# ArbPwrBoost_P4.net
KiCad netlist of a schematic drawn in Altium Designer
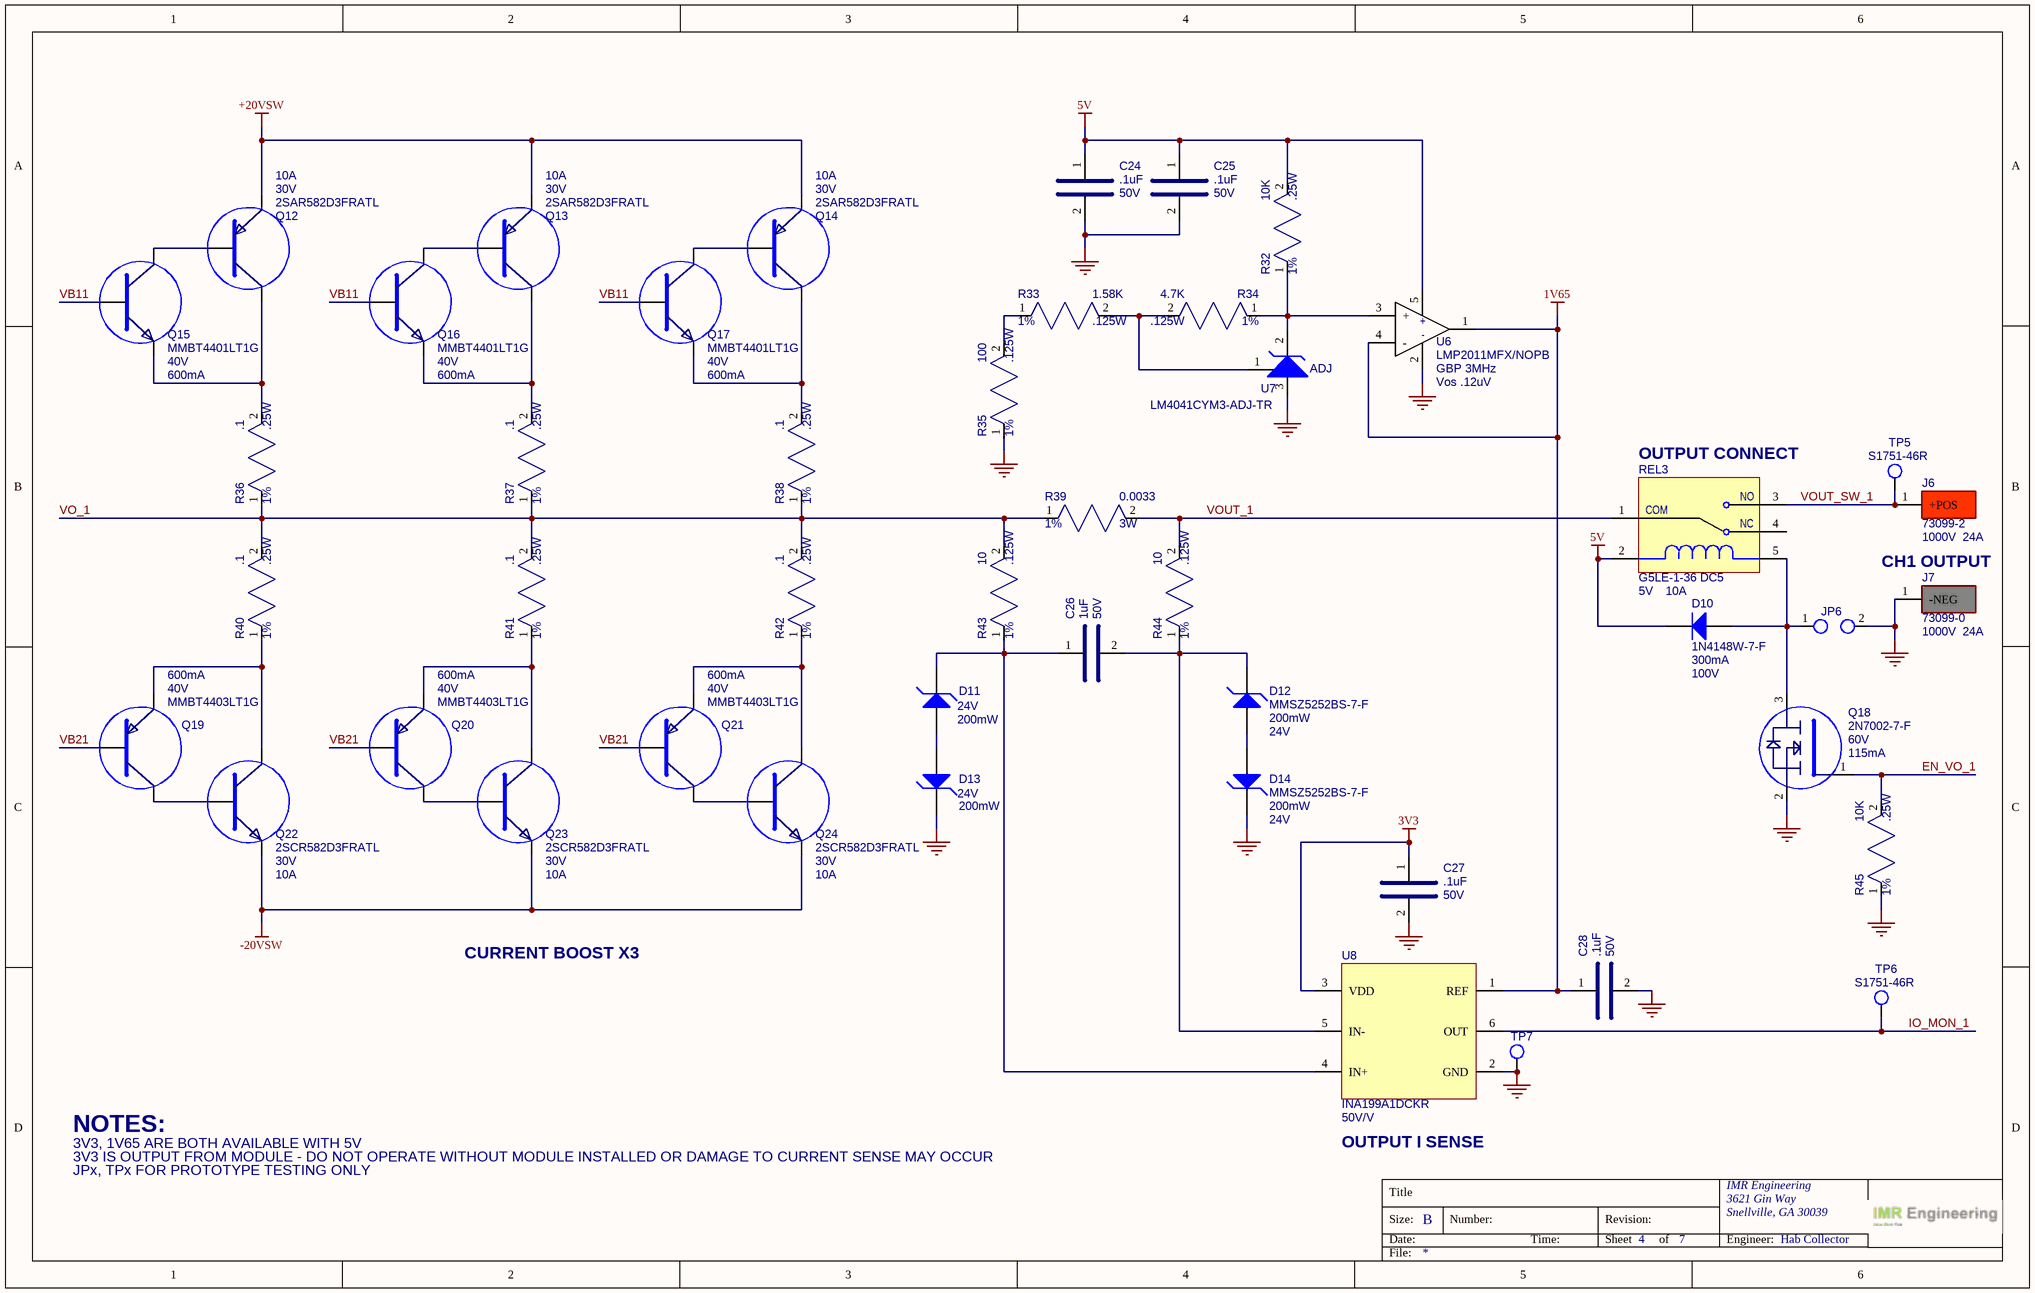
[diagram p0: ArbPwrBoost_P4.SchDoc]

(export (version "E")
  (design (tool "Eeschema 10.0.6"))
  (components
    (comp (ref "C24")
      (value ".1uF")
      (footprint "CAP_0805")
      (description "CAP CER 0.1UF 50V X7R 0805")
      (fields
        (field (name "MFG") "KYOCERA AVX")
        (field (name "VOLTAGE") "50V")
        (field (name "Comment") "KGM21NR71H104KT")
      )
      (libsource (lib "IMR_LIB_SCH_R2") (part "CAP_SMD_0.1UF_50V_0805"))
    )
    (comp (ref "C25")
      (value ".1uF")
      (footprint "CAP_0805")
      (description "CAP CER 0.1UF 50V X7R 0805")
      (fields
        (field (name "MFG") "KYOCERA AVX")
        (field (name "VOLTAGE") "50V")
        (field (name "Comment") "KGM21NR71H104KT")
      )
      (libsource (lib "IMR_LIB_SCH_R2") (part "CAP_SMD_0.1UF_50V_0805"))
    )
    (comp (ref "C26")
      (value "1uF")
      (footprint "CAP_0805")
      (description "CAP CER 1UF 50V X7R 0805")
      (fields
        (field (name "MFG") "KYOCERA AVX")
        (field (name "VOLTAGE") "50V")
        (field (name "Comment") "08055C105K4T2A")
      )
      (libsource (lib "IMR_LIB_SCH_R2") (part "CAP_SMD_1UF_50V_0805"))
    )
    (comp (ref "C27")
      (value ".1uF")
      (footprint "CAP_0805")
      (description "CAP CER 0.1UF 50V X7R 0805")
      (fields
        (field (name "MFG") "KYOCERA AVX")
        (field (name "VOLTAGE") "50V")
        (field (name "Comment") "KGM21NR71H104KT")
      )
      (libsource (lib "IMR_LIB_SCH_R2") (part "CAP_SMD_0.1UF_50V_0805"))
    )
    (comp (ref "C28")
      (value ".1uF")
      (footprint "CAP_0805")
      (description "CAP CER 0.1UF 50V X7R 0805")
      (fields
        (field (name "MFG") "KYOCERA AVX")
        (field (name "VOLTAGE") "50V")
        (field (name "Comment") "KGM21NR71H104KT")
      )
      (libsource (lib "IMR_LIB_SCH_R2") (part "CAP_SMD_0.1UF_50V_0805"))
    )
    (comp (ref "D10")
      (value "100V")
      (footprint "SOD123")
      (description "RELAY REED SPDT 250MA 5V")
      (fields
        (field (name "MFG") "Diodes Inc")
        (field (name "MFG_PN") "1N4148W-7-F")
        (field (name "CURRENT") "300mA")
        (field (name "Comment") "1N4148W-7-F")
      )
      (libsource (lib "IMR_LIB_SCH_R2") (part "DIODE_1N4148W-7-F"))
    )
    (comp (ref "D11")
      (value "24V")
      (footprint "SOD323")
      (description "DIODE ZENER 24V 200MW SOD323")
      (fields
        (field (name "MFG") "Diodes Inc")
        (field (name "POWER") "200mW")
        (field (name "Comment") "MMSZ5252BS-7-F")
      )
      (libsource (lib "IMR_LIB_SCH_R2") (part "DIODE_ZENER_MMSZ5252BS-7-F"))
    )
    (comp (ref "D12")
      (value "24V")
      (footprint "SOD323")
      (description "DIODE ZENER 24V 200MW SOD323")
      (fields
        (field (name "MFG") "Diodes Inc")
        (field (name "MFG_PN") "MMSZ5252BS-7-F")
        (field (name "POWER") "200mW")
        (field (name "Comment") "MMSZ5252BS-7-F")
      )
      (libsource (lib "IMR_LIB_SCH_R2") (part "DIODE_ZENER_MMSZ5252BS-7-F"))
    )
    (comp (ref "D13")
      (value "24V")
      (footprint "SOD323")
      (description "DIODE ZENER 24V 200MW SOD323")
      (fields
        (field (name "MFG") "Diodes Inc")
        (field (name "POWER") "200mW")
        (field (name "Comment") "MMSZ5252BS-7-F")
      )
      (libsource (lib "IMR_LIB_SCH_R2") (part "DIODE_ZENER_MMSZ5252BS-7-F"))
    )
    (comp (ref "D14")
      (value "24V")
      (footprint "SOD323")
      (description "DIODE ZENER 24V 200MW SOD323")
      (fields
        (field (name "MFG") "Diodes Inc")
        (field (name "MFG_PN") "MMSZ5252BS-7-F")
        (field (name "POWER") "200mW")
        (field (name "Comment") "MMSZ5252BS-7-F")
      )
      (libsource (lib "IMR_LIB_SCH_R2") (part "DIODE_ZENER_MMSZ5252BS-7-F"))
    )
    (comp (ref "J6")
      (value "1000V")
      (footprint "Pomona_73099-2")
      (description "CONN 4mm Banana Socket Right Angle PCB RED")
      (fields
        (field (name "MFG") "Pomona")
        (field (name "MFG_PN") "73099-2")
        (field (name "CURRENT") "24A")
        (field (name "Comment") "73099-2")
      )
      (libsource (lib "IMR_LIB_SCH_R2") (part "CONN_PANOMA_73099-2"))
    )
    (comp (ref "J7")
      (value "1000V")
      (footprint "Pomona_73099-0")
      (description "CONN 4mm Banana Socket Right Angle PCB BLK")
      (fields
        (field (name "MFG") "Pomona")
        (field (name "MFG_PN") "73099-0")
        (field (name "CURRENT") "24A")
        (field (name "Comment") "73099-0")
      )
      (libsource (lib "IMR_LIB_SCH_R2") (part "CONN_PANOMA_73099-0"))
    )
    (comp (ref "JP6")
      (value "PREC002SFAN-RC")
      (footprint "HDR_1X2_100MILL")
      (description "CONN HEADER VERT 2POS 2.54MM")
      (fields (field (name "MFG") "Sullins Connector Solutions"))
      (libsource (lib "IMR_LIB_SCH_R2") (part "CONN_JUMPER_2P_100MIL_VERT"))
    )
    (comp (ref "Q12")
      (value "30V")
      (footprint "TO-252")
      (description "TRANS PNP 30V 5.7A TO-252")
      (fields
        (field (name "MFG") "Rohm Semiconductor")
        (field (name "MFG_PN") "2SAR582D3FRATL")
        (field (name "CURRENT") "10A")
        (field (name "Comment") "2SAR582D3FRATL")
      )
      (libsource (lib "IMR_LIB_SCH_R2") (part "BJT_PNP_2SAR582D3FRATL"))
    )
    (comp (ref "Q13")
      (value "30V")
      (footprint "TO-252")
      (description "TRANS PNP 30V 5.7A TO-252")
      (fields
        (field (name "MFG") "Rohm Semiconductor")
        (field (name "MFG_PN") "2SAR582D3FRATL")
        (field (name "CURRENT") "10A")
        (field (name "Comment") "2SAR582D3FRATL")
      )
      (libsource (lib "IMR_LIB_SCH_R2") (part "BJT_PNP_2SAR582D3FRATL"))
    )
    (comp (ref "Q14")
      (value "30V")
      (footprint "TO-252")
      (description "TRANS PNP 30V 5.7A TO-252")
      (fields
        (field (name "MFG") "Rohm Semiconductor")
        (field (name "MFG_PN") "2SAR582D3FRATL")
        (field (name "CURRENT") "10A")
        (field (name "Comment") "2SAR582D3FRATL")
      )
      (libsource (lib "IMR_LIB_SCH_R2") (part "BJT_PNP_2SAR582D3FRATL"))
    )
    (comp (ref "Q15")
      (value "40V")
      (footprint "SOT-23")
      (description "TRANS NPN 40V 0.6A SOT23-3")
      (fields
        (field (name "MFG") "On Semiconductor")
        (field (name "MFG_PN") "MMBT4401LT1G")
        (field (name "CURRENT") "600mA")
        (field (name "Comment") "MMBT4401LT1G")
      )
      (libsource (lib "IMR_LIB_SCH_R2") (part "BJT_NPN_MMBT4401LT1G"))
    )
    (comp (ref "Q16")
      (value "40V")
      (footprint "SOT-23")
      (description "TRANS NPN 40V 0.6A SOT23-3")
      (fields
        (field (name "MFG") "On Semiconductor")
        (field (name "MFG_PN") "MMBT4401LT1G")
        (field (name "CURRENT") "600mA")
        (field (name "Comment") "MMBT4401LT1G")
      )
      (libsource (lib "IMR_LIB_SCH_R2") (part "BJT_NPN_MMBT4401LT1G"))
    )
    (comp (ref "Q17")
      (value "40V")
      (footprint "SOT-23")
      (description "TRANS NPN 40V 0.6A SOT23-3")
      (fields
        (field (name "MFG") "On Semiconductor")
        (field (name "MFG_PN") "MMBT4401LT1G")
        (field (name "CURRENT") "600mA")
        (field (name "Comment") "MMBT4401LT1G")
      )
      (libsource (lib "IMR_LIB_SCH_R2") (part "BJT_NPN_MMBT4401LT1G"))
    )
    (comp (ref "Q18")
      (value "60V")
      (footprint "SOT-23")
      (description "MOSFET N-CH 60V 115MA SOT23-3")
      (fields
        (field (name "MFG") "Diodes Inc")
        (field (name "MFG_PN") "2N7002-7-F")
        (field (name "CURRENT") "115mA")
        (field (name "Comment") "2N7002-7-F")
      )
      (libsource (lib "IMR_LIB_SCH_R2") (part "MOSFET_NCH_2N7002-7-F"))
    )
    (comp (ref "Q19")
      (value "40V")
      (footprint "SOT-23")
      (description "TRANS PNP 40V 0.6A SOT23-3")
      (fields
        (field (name "MFG") "On Semiconductor")
        (field (name "MFG_PN") "MMBT4403LT1G")
        (field (name "CURRENT") "600mA")
        (field (name "Comment") "MMBT4403LT1G")
      )
      (libsource (lib "IMR_LIB_SCH_R2") (part "BJT_PNP_MMBT4403LT1G"))
    )
    (comp (ref "Q20")
      (value "40V")
      (footprint "SOT-23")
      (description "TRANS PNP 40V 0.6A SOT23-3")
      (fields
        (field (name "MFG") "On Semiconductor")
        (field (name "MFG_PN") "MMBT4403LT1G")
        (field (name "CURRENT") "600mA")
        (field (name "Comment") "MMBT4403LT1G")
      )
      (libsource (lib "IMR_LIB_SCH_R2") (part "BJT_PNP_MMBT4403LT1G"))
    )
    (comp (ref "Q21")
      (value "40V")
      (footprint "SOT-23")
      (description "TRANS PNP 40V 0.6A SOT23-3")
      (fields
        (field (name "MFG") "On Semiconductor")
        (field (name "MFG_PN") "MMBT4403LT1G")
        (field (name "CURRENT") "600mA")
        (field (name "Comment") "MMBT4403LT1G")
      )
      (libsource (lib "IMR_LIB_SCH_R2") (part "BJT_PNP_MMBT4403LT1G"))
    )
    (comp (ref "Q22")
      (value "30V")
      (footprint "TO-252")
      (description "TRANS NPN 30V 10A TO-252")
      (fields
        (field (name "MFG") "Rohm Semiconductor")
        (field (name "MFG_PN") "2SCR582D3FRATL")
        (field (name "CURRENT") "10A")
        (field (name "Comment") "2SCR582D3FRATL")
      )
      (libsource (lib "IMR_LIB_SCH_R2") (part "BJT_NPN_2SCR582D3FRATL"))
    )
    (comp (ref "Q23")
      (value "30V")
      (footprint "TO-252")
      (description "TRANS NPN 30V 10A TO-252")
      (fields
        (field (name "MFG") "Rohm Semiconductor")
        (field (name "MFG_PN") "2SCR582D3FRATL")
        (field (name "CURRENT") "10A")
        (field (name "Comment") "2SCR582D3FRATL")
      )
      (libsource (lib "IMR_LIB_SCH_R2") (part "BJT_NPN_2SCR582D3FRATL"))
    )
    (comp (ref "Q24")
      (value "30V")
      (footprint "TO-252")
      (description "TRANS NPN 30V 10A TO-252")
      (fields
        (field (name "MFG") "Rohm Semiconductor")
        (field (name "MFG_PN") "2SCR582D3FRATL")
        (field (name "CURRENT") "10A")
        (field (name "Comment") "2SCR582D3FRATL")
      )
      (libsource (lib "IMR_LIB_SCH_R2") (part "BJT_NPN_2SCR582D3FRATL"))
    )
    (comp (ref "R32")
      (value "10K")
      (footprint "RES_0805")
      (description "RES SMD 10K OHM 1% 1/4W 0805")
      (fields
        (field (name "MFG") "Yageo")
        (field (name "POWER") ".25W")
        (field (name "TOLERANCE") "1%")
        (field (name "Comment") "RC0805FR-7W10KL")
      )
      (libsource (lib "IMR_LIB_SCH_R2") (part "RES_SMD_10K_0805_1/4W_1%"))
    )
    (comp (ref "R33")
      (value "1.58K")
      (footprint "RES_0805")
      (description "RES SMD 1.58K OHM 1% 1/8W 0805")
      (fields
        (field (name "MFG") "Yageo")
        (field (name "POWER") ".125W")
        (field (name "TOLERANCE") "1%")
        (field (name "Comment") "RC0805FR-071K58L")
      )
      (libsource (lib "IMR_LIB_SCH_R2") (part "RES_SMD_1.58K_0805_1/8W_1%"))
    )
    (comp (ref "R34")
      (value "4.7K")
      (footprint "RES_0805")
      (description "RES SMD 4.7K OHM 1% 1/8W 0805")
      (fields
        (field (name "MFG") "Yageo")
        (field (name "POWER") ".125W")
        (field (name "TOLERANCE") "1%")
        (field (name "Comment") "RC0805FR-134K7L")
      )
      (libsource (lib "IMR_LIB_SCH_R2") (part "RES_SMD_4.7K_0805_1/8W_1%"))
    )
    (comp (ref "R35")
      (value "100")
      (footprint "RES_0805")
      (description "RES SMD 100 OHM 1% 1/8W 0805")
      (fields
        (field (name "MFG") "Yageo")
        (field (name "POWER") ".125W")
        (field (name "TOLERANCE") "1%")
        (field (name "Comment") "RC0805FR-07100RL")
      )
      (libsource (lib "IMR_LIB_SCH_R2") (part "RES_SMD_100_0805_1/8W_1%"))
    )
    (comp (ref "R36")
      (value ".1")
      (footprint "RES_1206")
      (description "RES SMD 0.1 OHM 1% 1/4W 1206")
      (fields
        (field (name "MFG") "Yageo")
        (field (name "POWER") ".25W")
        (field (name "TOLERANCE") "1%")
        (field (name "Comment") "311-0.1LWCT-ND")
      )
      (libsource (lib "IMR_LIB_SCH_R2") (part "RES_SMD_0.1_1206_1/4W_1%"))
    )
    (comp (ref "R37")
      (value ".1")
      (footprint "RES_1206")
      (description "RES SMD 0.1 OHM 1% 1/4W 1206")
      (fields
        (field (name "MFG") "Yageo")
        (field (name "POWER") ".25W")
        (field (name "TOLERANCE") "1%")
        (field (name "Comment") "311-0.1LWCT-ND")
      )
      (libsource (lib "IMR_LIB_SCH_R2") (part "RES_SMD_0.1_1206_1/4W_1%"))
    )
    (comp (ref "R38")
      (value ".1")
      (footprint "RES_1206")
      (description "RES SMD 0.1 OHM 1% 1/4W 1206")
      (fields
        (field (name "MFG") "Yageo")
        (field (name "POWER") ".25W")
        (field (name "TOLERANCE") "1%")
        (field (name "Comment") "311-0.1LWCT-ND")
      )
      (libsource (lib "IMR_LIB_SCH_R2") (part "RES_SMD_0.1_1206_1/4W_1%"))
    )
    (comp (ref "R39")
      (value "0.0033")
      (footprint "RES_2512")
      (description "RES SMD 0.0033 OHM 1% 3W 2512")
      (fields
        (field (name "MFG") "Vishay Dale")
        (field (name "TOLERANCE") "1%")
        (field (name "POWER") "3W")
        (field (name "Comment") "WSLP25123L300FEA")
      )
      (libsource (lib "IMR_LIB_SCH_R2") (part "RES_SMD_0.0033_2512_3W_1%"))
    )
    (comp (ref "R40")
      (value ".1")
      (footprint "RES_1206")
      (description "RES SMD 0.1 OHM 1% 1/4W 1206")
      (fields
        (field (name "MFG") "Yageo")
        (field (name "POWER") ".25W")
        (field (name "TOLERANCE") "1%")
        (field (name "Comment") "311-0.1LWCT-ND")
      )
      (libsource (lib "IMR_LIB_SCH_R2") (part "RES_SMD_0.1_1206_1/4W_1%"))
    )
    (comp (ref "R41")
      (value ".1")
      (footprint "RES_1206")
      (description "RES SMD 0.1 OHM 1% 1/4W 1206")
      (fields
        (field (name "MFG") "Yageo")
        (field (name "POWER") ".25W")
        (field (name "TOLERANCE") "1%")
        (field (name "Comment") "311-0.1LWCT-ND")
      )
      (libsource (lib "IMR_LIB_SCH_R2") (part "RES_SMD_0.1_1206_1/4W_1%"))
    )
    (comp (ref "R42")
      (value ".1")
      (footprint "RES_1206")
      (description "RES SMD 0.1 OHM 1% 1/4W 1206")
      (fields
        (field (name "MFG") "Yageo")
        (field (name "POWER") ".25W")
        (field (name "TOLERANCE") "1%")
        (field (name "Comment") "311-0.1LWCT-ND")
      )
      (libsource (lib "IMR_LIB_SCH_R2") (part "RES_SMD_0.1_1206_1/4W_1%"))
    )
    (comp (ref "R43")
      (value "10")
      (footprint "RES_0805")
      (description "RES SMD 10 OHM 1% 1/8W 0805")
      (fields
        (field (name "MFG") "Yageo")
        (field (name "POWER") ".125W")
        (field (name "TOLERANCE") "1%")
        (field (name "Comment") "RC0805FR-1310RL")
      )
      (libsource (lib "IMR_LIB_SCH_R2") (part "RES_SMD_10_0805_1/8W_1%"))
    )
    (comp (ref "R44")
      (value "10")
      (footprint "RES_0805")
      (description "RES SMD 10 OHM 1% 1/8W 0805")
      (fields
        (field (name "MFG") "Yageo")
        (field (name "POWER") ".125W")
        (field (name "TOLERANCE") "1%")
        (field (name "Comment") "RC0805FR-1310RL")
      )
      (libsource (lib "IMR_LIB_SCH_R2") (part "RES_SMD_10_0805_1/8W_1%"))
    )
    (comp (ref "R45")
      (value "10K")
      (footprint "RES_0805")
      (description "RES SMD 10K OHM 1% 1/4W 0805")
      (fields
        (field (name "MFG") "Yageo")
        (field (name "POWER") ".25W")
        (field (name "TOLERANCE") "1%")
        (field (name "Comment") "RC0805FR-7W10KL")
      )
      (libsource (lib "IMR_LIB_SCH_R2") (part "RES_SMD_10K_0805_1/4W_1%"))
    )
    (comp (ref "REL3")
      (value "5V")
      (footprint "G5LE")
      (description "RELAY GEN PURPOSE SPDT 10A 5V")
      (fields
        (field (name "MFG") "Omron")
        (field (name "MFG_PN") "G5LE-1-36 DC5")
        (field (name "CURRENT") "10A")
        (field (name "Comment") "G5LE-1-36 DC5")
      )
      (libsource (lib "IMR_LIB_SCH_R2") (part "RELAY_G5LE-1-36 DC5"))
    )
    (comp (ref "TP5")
      (value "S1751-46R")
      (footprint "HARWIN_S1751")
      (description "PCB TEST POINT CONNECT")
      (fields (field (name "MFG") "Harwin Inc") (field (name "MFG_PN") "S1751-46R"))
      (libsource (lib "IMR_LIB_SCH_R2") (part "CONN_TEST_POINT_S1751-46R"))
    )
    (comp (ref "TP6")
      (value "S1751-46R")
      (footprint "HARWIN_S1751")
      (description "PCB TEST POINT CONNECT")
      (fields (field (name "MFG") "Harwin Inc") (field (name "MFG_PN") "S1751-46R"))
      (libsource (lib "IMR_LIB_SCH_R2") (part "CONN_TEST_POINT_S1751-46R"))
    )
    (comp (ref "TP7")
      (value "~")
      (footprint "TEST_POINT_20MIL_TH")
      (description "TEST POINT TH 20MIL HOLE")
      (libsource (lib "IMR_LIB_SCH_R2") (part "CONN_TEST_POINT_TH_PAD_20MIL"))
    )
    (comp (ref "U6")
      (value "GBP 3MHz")
      (footprint "SOT-23-5")
      (description "IC OPAMP GP 3MHZ .12uV CIRCUIT SOT23-5")
      (fields
        (field (name "MFG") "Texas Instruments")
        (field (name "MFG_PN") "LMP2011MFX/NOPB")
        (field (name "VOS") "Vos .12uV")
        (field (name "Comment") "LMP2011MFX/NOPB")
      )
      (libsource (lib "IMR_LIB_SCH_R2") (part "OPAMP_LMP2011MFX/NOPB"))
    )
    (comp (ref "U7")
      (value "ADJ")
      (footprint "SOT-23")
      (description "IC VREF SHUNT ADJ 0.5% SOT23-3")
      (fields
        (field (name "MFG") "Microchip")
        (field (name "MFG_PN") "LM4041CYM3-ADJ-TR")
        (field (name "Comment") "LM4041CYM3-ADJ-TR")
      )
      (libsource (lib "IMR_LIB_SCH_R2") (part "IC_LM4041CYM3-ADJ-TR"))
    )
    (comp (ref "U8")
      (value "50V/V")
      (footprint "SC-70-6")
      (description "IC CURRENT SENSE 1.5% 50V/V SC70-6")
      (fields
        (field (name "MFG") "Texas Instruments")
        (field (name "MFG_PN") "INA199A1DCKR")
        (field (name "Comment") "INA199A1DCKR")
      )
      (libsource (lib "IMR_LIB_SCH_R2") (part "IC_INA199A1DCKR"))
    )
  )
  (nets
    (net (code "1") (name "+20VSW") (class "Default")
      (node (ref "Q12") (pin "2") (pinfunction "E_2") (pintype "passive"))
      (node (ref "Q13") (pin "2") (pinfunction "E_2") (pintype "passive"))
      (node (ref "Q14") (pin "2") (pinfunction "E_2") (pintype "passive"))
    )
    (net (code "2") (name "-20VSW") (class "Default")
      (node (ref "Q22") (pin "2") (pinfunction "E_2") (pintype "passive"))
      (node (ref "Q23") (pin "2") (pinfunction "E_2") (pintype "passive"))
      (node (ref "Q24") (pin "2") (pinfunction "E_2") (pintype "passive"))
    )
    (net (code "3") (name "/EN_VO_1") (class "Default")
      (node (ref "Q18") (pin "1") (pinfunction "B_1") (pintype "passive"))
      (node (ref "R45") (pin "2") (pinfunction "2_2") (pintype "passive"))
    )
    (net (code "4") (name "/IO_MON_1") (class "Default")
      (node (ref "TP6") (pin "1") (pintype "passive"))
      (node (ref "U8") (pin "6") (pinfunction "OUT_6") (pintype "passive"))
    )
    (net (code "5") (name "/VB11") (class "Default")
      (node (ref "Q15") (pin "1") (pinfunction "B_1") (pintype "passive"))
      (node (ref "Q16") (pin "1") (pinfunction "B_1") (pintype "passive"))
      (node (ref "Q17") (pin "1") (pinfunction "B_1") (pintype "passive"))
    )
    (net (code "6") (name "/VB21") (class "Default")
      (node (ref "Q19") (pin "1") (pinfunction "B_1") (pintype "passive"))
      (node (ref "Q20") (pin "1") (pinfunction "B_1") (pintype "passive"))
      (node (ref "Q21") (pin "1") (pinfunction "B_1") (pintype "passive"))
    )
    (net (code "7") (name "/VOUT_1") (class "Default")
      (node (ref "R39") (pin "2") (pinfunction "2_2") (pintype "passive"))
      (node (ref "R44") (pin "2") (pinfunction "2_2") (pintype "passive"))
      (node (ref "REL3") (pin "1") (pinfunction "COM_1") (pintype "passive"))
    )
    (net (code "8") (name "/VOUT_SW_1") (class "Default")
      (node (ref "J6") (pin "1") (pinfunction "+POS_1") (pintype "passive"))
      (node (ref "REL3") (pin "3") (pinfunction "NO_3") (pintype "passive"))
      (node (ref "TP5") (pin "1") (pintype "passive"))
    )
    (net (code "9") (name "/VO_1") (class "Default")
      (node (ref "R36") (pin "1") (pinfunction "1_1") (pintype "passive"))
      (node (ref "R37") (pin "1") (pinfunction "1_1") (pintype "passive"))
      (node (ref "R38") (pin "1") (pinfunction "1_1") (pintype "passive"))
      (node (ref "R39") (pin "1") (pinfunction "1_1") (pintype "passive"))
      (node (ref "R40") (pin "2") (pinfunction "2_2") (pintype "passive"))
      (node (ref "R41") (pin "2") (pinfunction "2_2") (pintype "passive"))
      (node (ref "R42") (pin "2") (pinfunction "2_2") (pintype "passive"))
      (node (ref "R43") (pin "2") (pinfunction "2_2") (pintype "passive"))
    )
    (net (code "10") (name "1V65") (class "Default")
      (node (ref "C28") (pin "1") (pinfunction "1_1") (pintype "passive"))
      (node (ref "U6") (pin "1") (pintype "passive"))
      (node (ref "U6") (pin "4") (pinfunction "-_4") (pintype "passive"))
      (node (ref "U8") (pin "1") (pinfunction "REF_1") (pintype "passive"))
    )
    (net (code "11") (name "3V3") (class "Default")
      (node (ref "C27") (pin "1") (pinfunction "1_1") (pintype "passive"))
      (node (ref "U8") (pin "3") (pinfunction "VDD_3") (pintype "passive"))
    )
    (net (code "12") (name "5V") (class "Default")
      (node (ref "C24") (pin "1") (pinfunction "1_1") (pintype "passive"))
      (node (ref "C25") (pin "1") (pinfunction "1_1") (pintype "passive"))
      (node (ref "D10") (pin "2") (pinfunction "K_2") (pintype "passive"))
      (node (ref "R32") (pin "2") (pinfunction "2_2") (pintype "passive"))
      (node (ref "REL3") (pin "2") (pintype "passive"))
      (node (ref "U6") (pin "5") (pintype "passive"))
    )
    (net (code "13") (name "GND") (class "Default")
      (node (ref "C24") (pin "2") (pinfunction "2_2") (pintype "passive"))
      (node (ref "C25") (pin "2") (pinfunction "2_2") (pintype "passive"))
      (node (ref "C27") (pin "2") (pinfunction "2_2") (pintype "passive"))
      (node (ref "C28") (pin "2") (pinfunction "2_2") (pintype "passive"))
      (node (ref "D13") (pin "2") (pinfunction "K_2") (pintype "passive"))
      (node (ref "D14") (pin "2") (pinfunction "K_2") (pintype "passive"))
      (node (ref "J7") (pin "1") (pinfunction "-NEG_1") (pintype "passive"))
      (node (ref "JP6") (pin "2") (pintype "passive"))
      (node (ref "Q18") (pin "2") (pinfunction "E_2") (pintype "passive"))
      (node (ref "R35") (pin "1") (pinfunction "1_1") (pintype "passive"))
      (node (ref "R45") (pin "1") (pinfunction "1_1") (pintype "passive"))
      (node (ref "TP7") (pin "1") (pintype "passive"))
      (node (ref "U6") (pin "2") (pintype "passive"))
      (node (ref "U7") (pin "3") (pinfunction "A_3") (pintype "passive"))
      (node (ref "U8") (pin "2") (pinfunction "GND_2") (pintype "passive"))
    )
    (net (code "14") (name "Net-(D10-A)") (class "Default")
      (node (ref "D10") (pin "1") (pinfunction "A_1") (pintype "passive"))
      (node (ref "JP6") (pin "1") (pintype "passive"))
      (node (ref "Q18") (pin "3") (pinfunction "C_3") (pintype "passive"))
      (node (ref "REL3") (pin "5") (pintype "passive"))
    )
    (net (code "15") (name "Net-(D11-A)") (class "Default")
      (node (ref "D11") (pin "1") (pinfunction "A_1") (pintype "passive"))
      (node (ref "D13") (pin "1") (pinfunction "A_1") (pintype "passive"))
    )
    (net (code "16") (name "Net-(D11-K)") (class "Default")
      (node (ref "C26") (pin "1") (pinfunction "1_1") (pintype "passive"))
      (node (ref "D11") (pin "2") (pinfunction "K_2") (pintype "passive"))
      (node (ref "R43") (pin "1") (pinfunction "1_1") (pintype "passive"))
      (node (ref "U8") (pin "4") (pinfunction "IN+_4") (pintype "passive"))
    )
    (net (code "17") (name "Net-(D12-A)") (class "Default")
      (node (ref "D12") (pin "1") (pinfunction "A_1") (pintype "passive"))
      (node (ref "D14") (pin "1") (pinfunction "A_1") (pintype "passive"))
    )
    (net (code "18") (name "Net-(D12-K)") (class "Default")
      (node (ref "C26") (pin "2") (pinfunction "2_2") (pintype "passive"))
      (node (ref "D12") (pin "2") (pinfunction "K_2") (pintype "passive"))
      (node (ref "R44") (pin "1") (pinfunction "1_1") (pintype "passive"))
      (node (ref "U8") (pin "5") (pinfunction "IN-_5") (pintype "passive"))
    )
    (net (code "19") (name "Net-(Q12-B)") (class "Default")
      (node (ref "Q12") (pin "1") (pinfunction "B_1") (pintype "passive"))
      (node (ref "Q15") (pin "3") (pinfunction "C_3") (pintype "passive"))
    )
    (net (code "20") (name "Net-(Q12-C)") (class "Default")
      (node (ref "Q12") (pin "3") (pinfunction "C_3") (pintype "passive"))
      (node (ref "Q15") (pin "2") (pinfunction "E_2") (pintype "passive"))
      (node (ref "R36") (pin "2") (pinfunction "2_2") (pintype "passive"))
    )
    (net (code "21") (name "Net-(Q13-B)") (class "Default")
      (node (ref "Q13") (pin "1") (pinfunction "B_1") (pintype "passive"))
      (node (ref "Q16") (pin "3") (pinfunction "C_3") (pintype "passive"))
    )
    (net (code "22") (name "Net-(Q13-C)") (class "Default")
      (node (ref "Q13") (pin "3") (pinfunction "C_3") (pintype "passive"))
      (node (ref "Q16") (pin "2") (pinfunction "E_2") (pintype "passive"))
      (node (ref "R37") (pin "2") (pinfunction "2_2") (pintype "passive"))
    )
    (net (code "23") (name "Net-(Q14-B)") (class "Default")
      (node (ref "Q14") (pin "1") (pinfunction "B_1") (pintype "passive"))
      (node (ref "Q17") (pin "3") (pinfunction "C_3") (pintype "passive"))
    )
    (net (code "24") (name "Net-(Q14-C)") (class "Default")
      (node (ref "Q14") (pin "3") (pinfunction "C_3") (pintype "passive"))
      (node (ref "Q17") (pin "2") (pinfunction "E_2") (pintype "passive"))
      (node (ref "R38") (pin "2") (pinfunction "2_2") (pintype "passive"))
    )
    (net (code "25") (name "Net-(Q19-C)") (class "Default")
      (node (ref "Q19") (pin "3") (pinfunction "C_3") (pintype "passive"))
      (node (ref "Q22") (pin "1") (pinfunction "B_1") (pintype "passive"))
    )
    (net (code "26") (name "Net-(Q19-E)") (class "Default")
      (node (ref "Q19") (pin "2") (pinfunction "E_2") (pintype "passive"))
      (node (ref "Q22") (pin "3") (pinfunction "C_3") (pintype "passive"))
      (node (ref "R40") (pin "1") (pinfunction "1_1") (pintype "passive"))
    )
    (net (code "27") (name "Net-(Q20-C)") (class "Default")
      (node (ref "Q20") (pin "3") (pinfunction "C_3") (pintype "passive"))
      (node (ref "Q23") (pin "1") (pinfunction "B_1") (pintype "passive"))
    )
    (net (code "28") (name "Net-(Q20-E)") (class "Default")
      (node (ref "Q20") (pin "2") (pinfunction "E_2") (pintype "passive"))
      (node (ref "Q23") (pin "3") (pinfunction "C_3") (pintype "passive"))
      (node (ref "R41") (pin "1") (pinfunction "1_1") (pintype "passive"))
    )
    (net (code "29") (name "Net-(Q21-C)") (class "Default")
      (node (ref "Q21") (pin "3") (pinfunction "C_3") (pintype "passive"))
      (node (ref "Q24") (pin "1") (pinfunction "B_1") (pintype "passive"))
    )
    (net (code "30") (name "Net-(Q21-E)") (class "Default")
      (node (ref "Q21") (pin "2") (pinfunction "E_2") (pintype "passive"))
      (node (ref "Q24") (pin "3") (pinfunction "C_3") (pintype "passive"))
      (node (ref "R42") (pin "1") (pinfunction "1_1") (pintype "passive"))
    )
    (net (code "31") (name "Net-(R33-Pad1)") (class "Default")
      (node (ref "R33") (pin "1") (pinfunction "1_1") (pintype "passive"))
      (node (ref "R35") (pin "2") (pinfunction "2_2") (pintype "passive"))
    )
    (net (code "32") (name "Net-(U6-+)") (class "Default")
      (node (ref "R32") (pin "1") (pinfunction "1_1") (pintype "passive"))
      (node (ref "R34") (pin "1") (pinfunction "1_1") (pintype "passive"))
      (node (ref "U6") (pin "3") (pinfunction "+_3") (pintype "passive"))
      (node (ref "U7") (pin "2") (pinfunction "K_2") (pintype "passive"))
    )
    (net (code "33") (name "Net-(U7-FB)") (class "Default")
      (node (ref "R33") (pin "2") (pinfunction "2_2") (pintype "passive"))
      (node (ref "R34") (pin "2") (pinfunction "2_2") (pintype "passive"))
      (node (ref "U7") (pin "1") (pinfunction "FB_1") (pintype "passive"))
    )
    (net (code "34") (name "unconnected-(REL3-NC-Pad4)") (class "Default")
      (node (ref "REL3") (pin "4") (pinfunction "NC_4") (pintype "passive"))
    )
  )
)
